# Relay_Sequencer.net
KiCad netlist of a schematic drawn in EAGLE
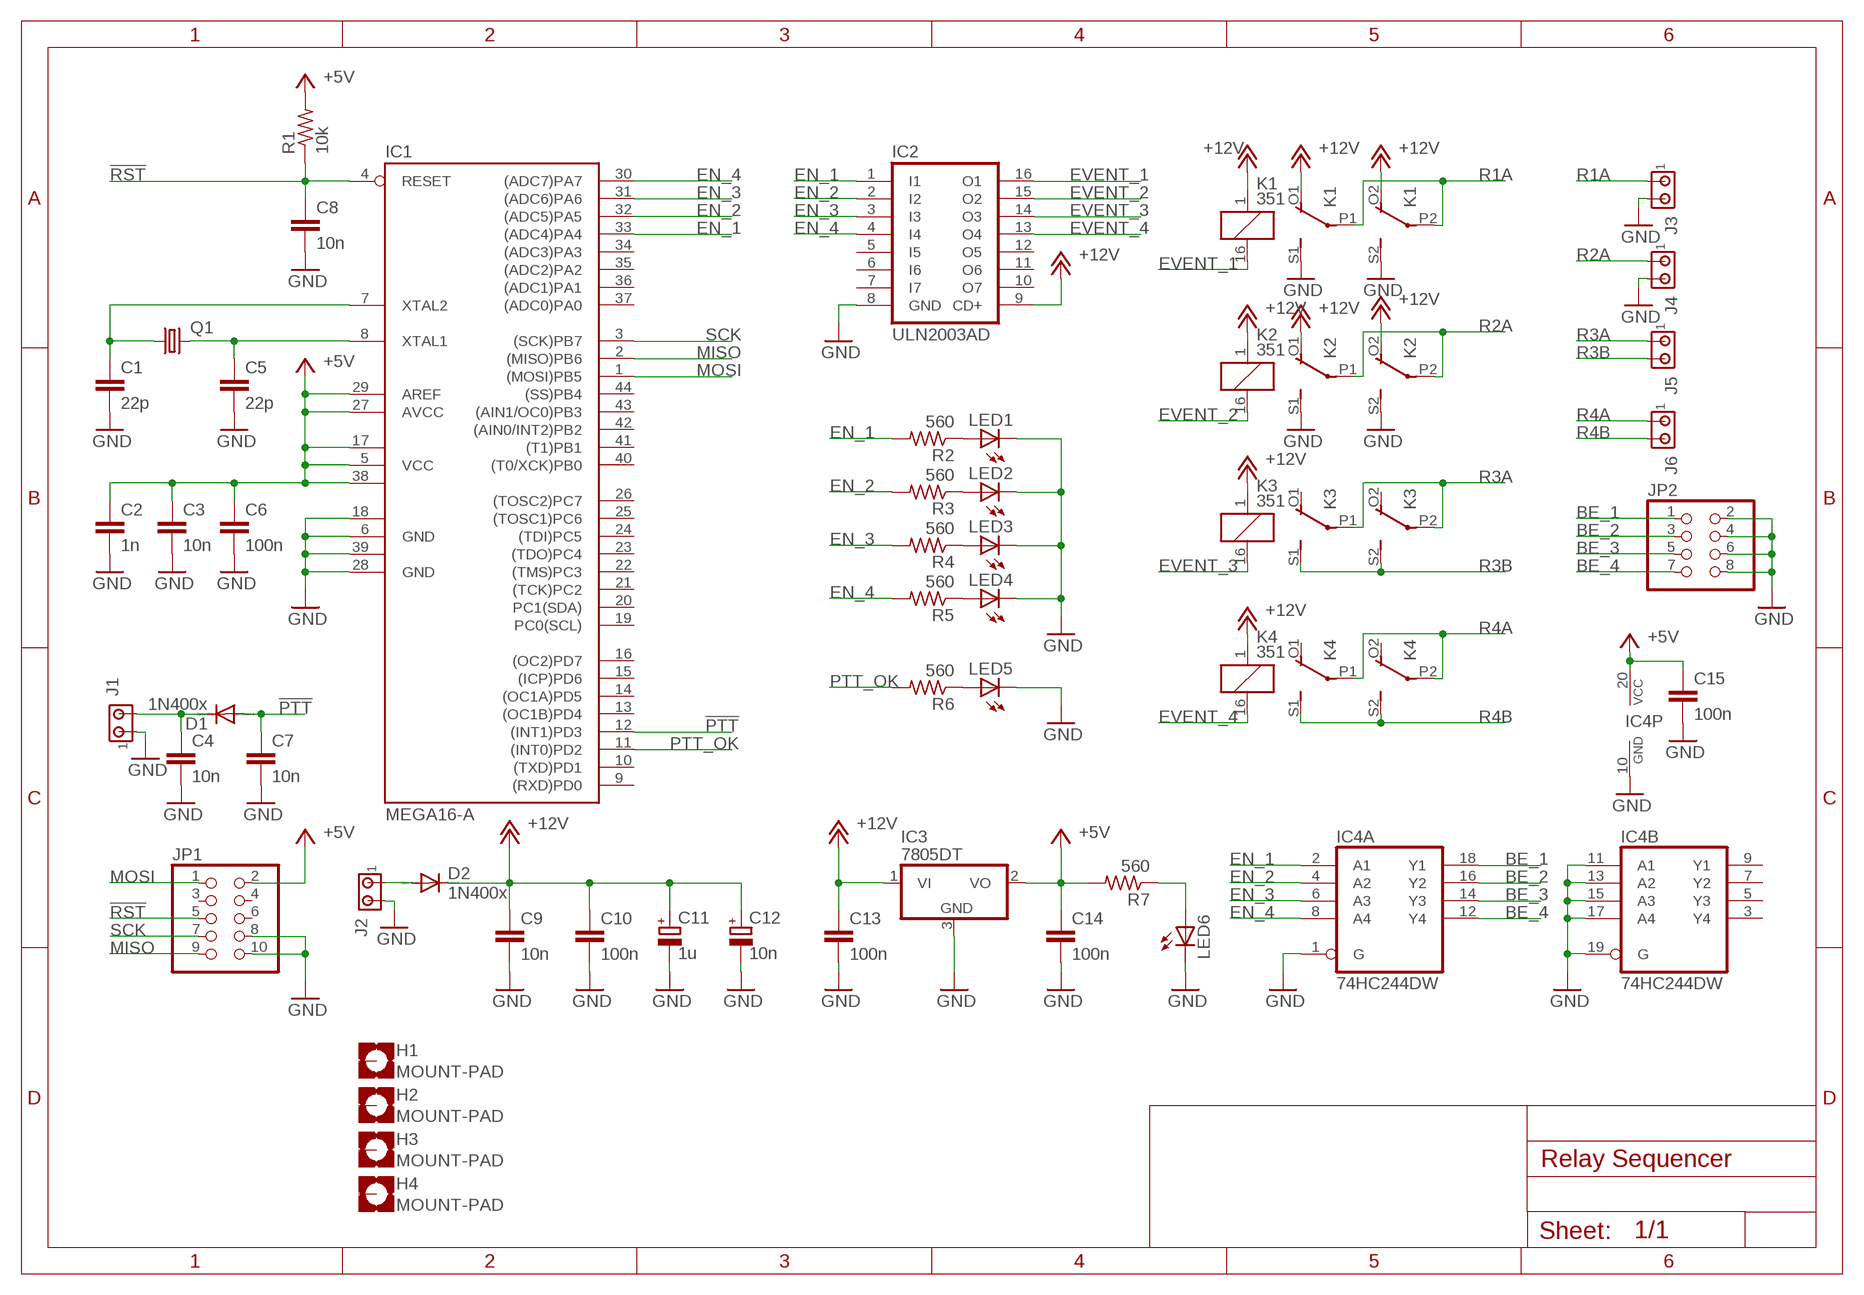
[diagram p0: schematic, sheet 1]

(export (version "E")
  (design (tool "Eeschema 10.0.6"))
  (components
    (comp (ref "C1")
      (value "22p")
      (footprint "eagle-import:C1206")
      (libsource (lib "eagle-import") (part "C-EUC1206"))
    )
    (comp (ref "C2")
      (value "1n")
      (footprint "eagle-import:C1206")
      (libsource (lib "eagle-import") (part "C-EUC1206"))
    )
    (comp (ref "C3")
      (value "10n")
      (footprint "eagle-import:C1206")
      (libsource (lib "eagle-import") (part "C-EUC1206"))
    )
    (comp (ref "C4")
      (value "10n")
      (footprint "eagle-import:C1206")
      (libsource (lib "eagle-import") (part "C-EUC1206"))
    )
    (comp (ref "C5")
      (value "22p")
      (footprint "eagle-import:C1206")
      (libsource (lib "eagle-import") (part "C-EUC1206"))
    )
    (comp (ref "C6")
      (value "100n")
      (footprint "eagle-import:C1206")
      (libsource (lib "eagle-import") (part "C-EUC1206"))
    )
    (comp (ref "C7")
      (value "10n")
      (footprint "eagle-import:C1206")
      (libsource (lib "eagle-import") (part "C-EUC1206"))
    )
    (comp (ref "C8")
      (value "10n")
      (footprint "eagle-import:C1206")
      (libsource (lib "eagle-import") (part "C-EUC1206"))
    )
    (comp (ref "C9")
      (value "10n")
      (footprint "eagle-import:C1206")
      (libsource (lib "eagle-import") (part "C-EUC1206"))
    )
    (comp (ref "C10")
      (value "100n")
      (footprint "eagle-import:C1206")
      (libsource (lib "eagle-import") (part "C-EUC1206"))
    )
    (comp (ref "C11")
      (value "1u")
      (footprint "eagle-import:E5-8,5")
      (libsource (lib "eagle-import") (part "CPOL-EUE5-8.5"))
    )
    (comp (ref "C12")
      (value "10n")
      (footprint "eagle-import:E5-13")
      (libsource (lib "eagle-import") (part "CPOL-EUE5-13"))
    )
    (comp (ref "C13")
      (value "100n")
      (footprint "eagle-import:C1206")
      (libsource (lib "eagle-import") (part "C-EUC1206"))
    )
    (comp (ref "C14")
      (value "100n")
      (footprint "eagle-import:C1206")
      (libsource (lib "eagle-import") (part "C-EUC1206"))
    )
    (comp (ref "C15")
      (value "100n")
      (footprint "eagle-import:C1206")
      (libsource (lib "eagle-import") (part "C-EUC1206"))
    )
    (comp (ref "D1")
      (value "1N400x")
      (footprint "eagle-import:DO35-10")
      (libsource (lib "eagle-import") (part "1N4148DO35-10"))
    )
    (comp (ref "D2")
      (value "1N400x")
      (footprint "eagle-import:DO35-10")
      (libsource (lib "eagle-import") (part "1N4148DO35-10"))
    )
    (comp (ref "H1")
      (value "MOUNT-PAD")
      (footprint "eagle-import:2,8-PAD-SQUARE")
      (libsource (lib "eagle-import") (part "MOUNT-PAD-SQUARE2.8"))
    )
    (comp (ref "H2")
      (value "MOUNT-PAD")
      (footprint "eagle-import:2,8-PAD-SQUARE")
      (libsource (lib "eagle-import") (part "MOUNT-PAD-SQUARE2.8"))
    )
    (comp (ref "H3")
      (value "MOUNT-PAD")
      (footprint "eagle-import:2,8-PAD-SQUARE")
      (libsource (lib "eagle-import") (part "MOUNT-PAD-SQUARE2.8"))
    )
    (comp (ref "H4")
      (value "MOUNT-PAD")
      (footprint "eagle-import:2,8-PAD-SQUARE")
      (libsource (lib "eagle-import") (part "MOUNT-PAD-SQUARE2.8"))
    )
    (comp (ref "IC1")
      (value "MEGA16-A")
      (footprint "eagle-import:TQFP44")
      (fields (field (name "MPN") "ATMEGA16-16AU"))
      (libsource (lib "eagle-import") (part "MEGA16-A"))
    )
    (comp (ref "IC2")
      (value "ULN2003AD")
      (footprint "eagle-import:SO16")
      (libsource (lib "eagle-import") (part "ULN2003AD"))
    )
    (comp (ref "IC3")
      (value "7805DT")
      (footprint "eagle-import:TO252")
      (libsource (lib "eagle-import") (part "78DT05"))
    )
    (comp (ref "IC4")
      (value "74HC244DW")
      (footprint "eagle-import:SO20W")
      (libsource (lib "eagle-import") (part "74244DWHC"))
    )
    (comp (ref "J1")
      (value "MTA02-156")
      (footprint "eagle-import:1X2MTA")
      (libsource (lib "eagle-import") (part "MTA02-156"))
    )
    (comp (ref "J2")
      (value "MTA02-156")
      (footprint "eagle-import:1X2MTA")
      (libsource (lib "eagle-import") (part "MTA02-156"))
    )
    (comp (ref "J3")
      (value "MTA02-156")
      (footprint "eagle-import:1X2MTA")
      (libsource (lib "eagle-import") (part "MTA02-156"))
    )
    (comp (ref "J4")
      (value "MTA02-156")
      (footprint "eagle-import:1X2MTA")
      (libsource (lib "eagle-import") (part "MTA02-156"))
    )
    (comp (ref "J5")
      (value "MTA02-156")
      (footprint "eagle-import:1X2MTA")
      (libsource (lib "eagle-import") (part "MTA02-156"))
    )
    (comp (ref "J6")
      (value "MTA02-156")
      (footprint "eagle-import:1X2MTA")
      (libsource (lib "eagle-import") (part "MTA02-156"))
    )
    (comp (ref "JP1")
      (value "PINHD-2X5")
      (footprint "eagle-import:2X05")
      (libsource (lib "eagle-import") (part "PINHD-2X5"))
    )
    (comp (ref "JP2")
      (value "PINHD-2X4")
      (footprint "eagle-import:2X04")
      (libsource (lib "eagle-import") (part "PINHD-2X4"))
    )
    (comp (ref "K1")
      (value "351")
      (footprint "eagle-import:351")
      (libsource (lib "eagle-import") (part "351"))
    )
    (comp (ref "K2")
      (value "351")
      (footprint "eagle-import:351")
      (libsource (lib "eagle-import") (part "351"))
    )
    (comp (ref "K3")
      (value "351")
      (footprint "eagle-import:351")
      (libsource (lib "eagle-import") (part "351"))
    )
    (comp (ref "K4")
      (value "351")
      (footprint "eagle-import:351")
      (libsource (lib "eagle-import") (part "351"))
    )
    (comp (ref "LED1")
      (value "LED3MM")
      (footprint "eagle-import:LED3MM")
      (libsource (lib "eagle-import") (part "LED3MM"))
    )
    (comp (ref "LED2")
      (value "LED3MM")
      (footprint "eagle-import:LED3MM")
      (libsource (lib "eagle-import") (part "LED3MM"))
    )
    (comp (ref "LED3")
      (value "LED3MM")
      (footprint "eagle-import:LED3MM")
      (libsource (lib "eagle-import") (part "LED3MM"))
    )
    (comp (ref "LED4")
      (value "LED3MM")
      (footprint "eagle-import:LED3MM")
      (libsource (lib "eagle-import") (part "LED3MM"))
    )
    (comp (ref "LED5")
      (value "LED3MM")
      (footprint "eagle-import:LED3MM")
      (libsource (lib "eagle-import") (part "LED3MM"))
    )
    (comp (ref "LED6")
      (value "LED3MM")
      (footprint "eagle-import:LED3MM")
      (libsource (lib "eagle-import") (part "LED3MM"))
    )
    (comp (ref "Q1")
      (value "CRYSTALHC49S")
      (footprint "eagle-import:HC49_S")
      (libsource (lib "eagle-import") (part "CRYSTALHC49S"))
    )
    (comp (ref "R1")
      (value "10k")
      (footprint "eagle-import:M1206")
      (libsource (lib "eagle-import") (part "R-US_M1206"))
    )
    (comp (ref "R2")
      (value "560")
      (footprint "eagle-import:M1206")
      (libsource (lib "eagle-import") (part "R-US_M1206"))
    )
    (comp (ref "R3")
      (value "560")
      (footprint "eagle-import:M1206")
      (libsource (lib "eagle-import") (part "R-US_M1206"))
    )
    (comp (ref "R4")
      (value "560")
      (footprint "eagle-import:M1206")
      (libsource (lib "eagle-import") (part "R-US_M1206"))
    )
    (comp (ref "R5")
      (value "560")
      (footprint "eagle-import:M1206")
      (libsource (lib "eagle-import") (part "R-US_M1206"))
    )
    (comp (ref "R6")
      (value "560")
      (footprint "eagle-import:M1206")
      (libsource (lib "eagle-import") (part "R-US_M1206"))
    )
    (comp (ref "R7")
      (value "560")
      (footprint "eagle-import:M1206")
      (libsource (lib "eagle-import") (part "R-US_M1206"))
    )
  )
  (nets
    (net (code "1") (name "+5V") (class "Default")
      (node (ref "C14") (pin "1") (pinfunction "1_1") (pintype "passive"))
      (node (ref "C15") (pin "1") (pinfunction "1_1") (pintype "passive"))
      (node (ref "C2") (pin "1") (pinfunction "1_1") (pintype "passive"))
      (node (ref "C3") (pin "1") (pinfunction "1_1") (pintype "passive"))
      (node (ref "C6") (pin "1") (pinfunction "1_1") (pintype "passive"))
      (node (ref "IC1") (pin "17") (pinfunction "VCC1_17") (pintype "power_in"))
      (node (ref "IC1") (pin "27") (pinfunction "AVCC_27") (pintype "power_in"))
      (node (ref "IC1") (pin "29") (pinfunction "AREF_29") (pintype "passive"))
      (node (ref "IC1") (pin "38") (pinfunction "VCC2_38") (pintype "power_in"))
      (node (ref "IC1") (pin "5") (pinfunction "VCC_5") (pintype "power_in"))
      (node (ref "IC3") (pin "2") (pinfunction "VO_2") (pintype "passive"))
      (node (ref "IC4") (pin "20") (pinfunction "VCC_20") (pintype "power_in"))
      (node (ref "JP1") (pin "2") (pinfunction "2_2") (pintype "passive"))
      (node (ref "R1") (pin "2") (pinfunction "2_2") (pintype "passive"))
      (node (ref "R7") (pin "2") (pinfunction "2_2") (pintype "passive"))
    )
    (net (code "2") (name "+12V") (class "Default")
      (node (ref "C10") (pin "1") (pinfunction "1_1") (pintype "passive"))
      (node (ref "C11") (pin "+") (pinfunction "+_+") (pintype "passive"))
      (node (ref "C12") (pin "+") (pinfunction "+_+") (pintype "passive"))
      (node (ref "C13") (pin "1") (pinfunction "1_1") (pintype "passive"))
      (node (ref "C9") (pin "1") (pinfunction "1_1") (pintype "passive"))
      (node (ref "D2") (pin "C") (pinfunction "C_C") (pintype "passive"))
      (node (ref "IC2") (pin "9") (pinfunction "CD+_9") (pintype "passive"))
      (node (ref "IC3") (pin "1") (pinfunction "VI_1") (pintype "input"))
      (node (ref "K1") (pin "1") (pinfunction "1_1") (pintype "passive"))
      (node (ref "K1") (pin "O1") (pinfunction "O_O1") (pintype "passive"))
      (node (ref "K1") (pin "O2") (pinfunction "O_O2") (pintype "passive"))
      (node (ref "K2") (pin "1") (pinfunction "1_1") (pintype "passive"))
      (node (ref "K2") (pin "O1") (pinfunction "O_O1") (pintype "passive"))
      (node (ref "K2") (pin "O2") (pinfunction "O_O2") (pintype "passive"))
      (node (ref "K3") (pin "1") (pinfunction "1_1") (pintype "passive"))
      (node (ref "K4") (pin "1") (pinfunction "1_1") (pintype "passive"))
    )
    (net (code "3") (name "/BE_1") (class "Default")
      (node (ref "IC4") (pin "18") (pinfunction "Y1_18") (pintype "tri_state"))
      (node (ref "JP2") (pin "1") (pinfunction "1_1") (pintype "passive"))
    )
    (net (code "4") (name "/BE_2") (class "Default")
      (node (ref "IC4") (pin "16") (pinfunction "Y2_16") (pintype "tri_state"))
      (node (ref "JP2") (pin "3") (pinfunction "3_3") (pintype "passive"))
    )
    (net (code "5") (name "/BE_3") (class "Default")
      (node (ref "IC4") (pin "14") (pinfunction "Y3_14") (pintype "tri_state"))
      (node (ref "JP2") (pin "5") (pinfunction "5_5") (pintype "passive"))
    )
    (net (code "6") (name "/BE_4") (class "Default")
      (node (ref "IC4") (pin "12") (pinfunction "Y4_12") (pintype "tri_state"))
      (node (ref "JP2") (pin "7") (pinfunction "7_7") (pintype "passive"))
    )
    (net (code "7") (name "/EN_1") (class "Default")
      (node (ref "IC1") (pin "33") (pinfunction "(ADC4)PA4_33") (pintype "bidirectional"))
      (node (ref "IC2") (pin "1") (pinfunction "I1_1") (pintype "input"))
      (node (ref "IC4") (pin "2") (pinfunction "A1_2") (pintype "input"))
      (node (ref "R2") (pin "2") (pinfunction "2_2") (pintype "passive"))
    )
    (net (code "8") (name "/EN_2") (class "Default")
      (node (ref "IC1") (pin "32") (pinfunction "(ADC5)PA5_32") (pintype "bidirectional"))
      (node (ref "IC2") (pin "2") (pinfunction "I2_2") (pintype "input"))
      (node (ref "IC4") (pin "4") (pinfunction "A2_4") (pintype "input"))
      (node (ref "R3") (pin "2") (pinfunction "2_2") (pintype "passive"))
    )
    (net (code "9") (name "/EN_3") (class "Default")
      (node (ref "IC1") (pin "31") (pinfunction "(ADC6)PA6_31") (pintype "bidirectional"))
      (node (ref "IC2") (pin "3") (pinfunction "I3_3") (pintype "input"))
      (node (ref "IC4") (pin "6") (pinfunction "A3_6") (pintype "input"))
      (node (ref "R4") (pin "2") (pinfunction "2_2") (pintype "passive"))
    )
    (net (code "10") (name "/EN_4") (class "Default")
      (node (ref "IC1") (pin "30") (pinfunction "(ADC7)PA7_30") (pintype "bidirectional"))
      (node (ref "IC2") (pin "4") (pinfunction "I4_4") (pintype "input"))
      (node (ref "IC4") (pin "8") (pinfunction "A4_8") (pintype "input"))
      (node (ref "R5") (pin "2") (pinfunction "2_2") (pintype "passive"))
    )
    (net (code "11") (name "/EVENT_1") (class "Default")
      (node (ref "IC2") (pin "16") (pinfunction "O1_16") (pintype "open_collector"))
      (node (ref "K1") (pin "16") (pinfunction "2_16") (pintype "passive"))
    )
    (net (code "12") (name "/EVENT_2") (class "Default")
      (node (ref "IC2") (pin "15") (pinfunction "O2_15") (pintype "open_collector"))
      (node (ref "K2") (pin "16") (pinfunction "2_16") (pintype "passive"))
    )
    (net (code "13") (name "/EVENT_3") (class "Default")
      (node (ref "IC2") (pin "14") (pinfunction "O3_14") (pintype "open_collector"))
      (node (ref "K3") (pin "16") (pinfunction "2_16") (pintype "passive"))
    )
    (net (code "14") (name "/EVENT_4") (class "Default")
      (node (ref "IC2") (pin "13") (pinfunction "O4_13") (pintype "open_collector"))
      (node (ref "K4") (pin "16") (pinfunction "2_16") (pintype "passive"))
    )
    (net (code "15") (name "/MISO") (class "Default")
      (node (ref "IC1") (pin "2") (pinfunction "(MISO)PB6_2") (pintype "bidirectional"))
      (node (ref "JP1") (pin "9") (pinfunction "9_9") (pintype "passive"))
    )
    (net (code "16") (name "/MOSI") (class "Default")
      (node (ref "IC1") (pin "1") (pinfunction "(MOSI)PB5_1") (pintype "bidirectional"))
      (node (ref "JP1") (pin "1") (pinfunction "1_1") (pintype "passive"))
    )
    (net (code "17") (name "/PTT_OK") (class "Default")
      (node (ref "IC1") (pin "11") (pinfunction "(INT0)PD2_11") (pintype "bidirectional"))
      (node (ref "R6") (pin "2") (pinfunction "2_2") (pintype "passive"))
    )
    (net (code "18") (name "/R1A") (class "Default")
      (node (ref "J3") (pin "1") (pinfunction "1_1") (pintype "passive"))
      (node (ref "K1") (pin "P1") (pinfunction "P_P1") (pintype "passive"))
      (node (ref "K1") (pin "P2") (pinfunction "P_P2") (pintype "passive"))
    )
    (net (code "19") (name "/R2A") (class "Default")
      (node (ref "J4") (pin "1") (pinfunction "1_1") (pintype "passive"))
      (node (ref "K2") (pin "P1") (pinfunction "P_P1") (pintype "passive"))
      (node (ref "K2") (pin "P2") (pinfunction "P_P2") (pintype "passive"))
    )
    (net (code "20") (name "/R3A") (class "Default")
      (node (ref "J5") (pin "1") (pinfunction "1_1") (pintype "passive"))
      (node (ref "K3") (pin "P1") (pinfunction "P_P1") (pintype "passive"))
      (node (ref "K3") (pin "P2") (pinfunction "P_P2") (pintype "passive"))
    )
    (net (code "21") (name "/R3B") (class "Default")
      (node (ref "J5") (pin "2") (pinfunction "2_2") (pintype "passive"))
      (node (ref "K3") (pin "S1") (pinfunction "S_S1") (pintype "passive"))
      (node (ref "K3") (pin "S2") (pinfunction "S_S2") (pintype "passive"))
    )
    (net (code "22") (name "/R4A") (class "Default")
      (node (ref "J6") (pin "1") (pinfunction "1_1") (pintype "passive"))
      (node (ref "K4") (pin "P1") (pinfunction "P_P1") (pintype "passive"))
      (node (ref "K4") (pin "P2") (pinfunction "P_P2") (pintype "passive"))
    )
    (net (code "23") (name "/R4B") (class "Default")
      (node (ref "J6") (pin "2") (pinfunction "2_2") (pintype "passive"))
      (node (ref "K4") (pin "S1") (pinfunction "S_S1") (pintype "passive"))
      (node (ref "K4") (pin "S2") (pinfunction "S_S2") (pintype "passive"))
    )
    (net (code "24") (name "/SCK") (class "Default")
      (node (ref "IC1") (pin "3") (pinfunction "(SCK)PB7_3") (pintype "bidirectional"))
      (node (ref "JP1") (pin "7") (pinfunction "7_7") (pintype "passive"))
    )
    (net (code "25") (name "/~{PTT}") (class "Default")
      (node (ref "C7") (pin "1") (pinfunction "1_1") (pintype "passive"))
      (node (ref "D1") (pin "A") (pinfunction "A_A") (pintype "passive"))
      (node (ref "IC1") (pin "12") (pinfunction "(INT1)PD3_12") (pintype "bidirectional"))
    )
    (net (code "26") (name "/~{RST}") (class "Default")
      (node (ref "C8") (pin "1") (pinfunction "1_1") (pintype "passive"))
      (node (ref "IC1") (pin "4") (pinfunction "RESET_4") (pintype "input"))
      (node (ref "JP1") (pin "5") (pinfunction "5_5") (pintype "passive"))
      (node (ref "R1") (pin "1") (pinfunction "1_1") (pintype "passive"))
    )
    (net (code "27") (name "GND") (class "Default")
      (node (ref "C1") (pin "2") (pinfunction "2_2") (pintype "passive"))
      (node (ref "C10") (pin "2") (pinfunction "2_2") (pintype "passive"))
      (node (ref "C11") (pin "-") (pinfunction "-_-") (pintype "passive"))
      (node (ref "C12") (pin "-") (pinfunction "-_-") (pintype "passive"))
      (node (ref "C13") (pin "2") (pinfunction "2_2") (pintype "passive"))
      (node (ref "C14") (pin "2") (pinfunction "2_2") (pintype "passive"))
      (node (ref "C15") (pin "2") (pinfunction "2_2") (pintype "passive"))
      (node (ref "C2") (pin "2") (pinfunction "2_2") (pintype "passive"))
      (node (ref "C3") (pin "2") (pinfunction "2_2") (pintype "passive"))
      (node (ref "C4") (pin "2") (pinfunction "2_2") (pintype "passive"))
      (node (ref "C5") (pin "2") (pinfunction "2_2") (pintype "passive"))
      (node (ref "C6") (pin "2") (pinfunction "2_2") (pintype "passive"))
      (node (ref "C7") (pin "2") (pinfunction "2_2") (pintype "passive"))
      (node (ref "C8") (pin "2") (pinfunction "2_2") (pintype "passive"))
      (node (ref "C9") (pin "2") (pinfunction "2_2") (pintype "passive"))
      (node (ref "IC1") (pin "18") (pinfunction "GND1_18") (pintype "power_in"))
      (node (ref "IC1") (pin "28") (pinfunction "GND_28") (pintype "power_in"))
      (node (ref "IC1") (pin "39") (pinfunction "GND2_39") (pintype "power_in"))
      (node (ref "IC1") (pin "6") (pinfunction "GND_6") (pintype "power_in"))
      (node (ref "IC2") (pin "8") (pinfunction "GND_8") (pintype "power_in"))
      (node (ref "IC3") (pin "3") (pinfunction "GND_3") (pintype "passive"))
      (node (ref "IC4") (pin "1") (pinfunction "G_1") (pintype "input"))
      (node (ref "IC4") (pin "10") (pinfunction "GND_10") (pintype "power_in"))
      (node (ref "IC4") (pin "11") (pinfunction "A1_11") (pintype "input"))
      (node (ref "IC4") (pin "13") (pinfunction "A2_13") (pintype "input"))
      (node (ref "IC4") (pin "15") (pinfunction "A3_15") (pintype "input"))
      (node (ref "IC4") (pin "17") (pinfunction "A4_17") (pintype "input"))
      (node (ref "IC4") (pin "19") (pinfunction "G_19") (pintype "input"))
      (node (ref "J1") (pin "1") (pinfunction "1_1") (pintype "passive"))
      (node (ref "J2") (pin "2") (pinfunction "2_2") (pintype "passive"))
      (node (ref "J3") (pin "2") (pinfunction "2_2") (pintype "passive"))
      (node (ref "J4") (pin "2") (pinfunction "2_2") (pintype "passive"))
      (node (ref "JP1") (pin "10") (pinfunction "10_10") (pintype "passive"))
      (node (ref "JP1") (pin "8") (pinfunction "8_8") (pintype "passive"))
      (node (ref "JP2") (pin "2") (pinfunction "2_2") (pintype "passive"))
      (node (ref "JP2") (pin "4") (pinfunction "4_4") (pintype "passive"))
      (node (ref "JP2") (pin "6") (pinfunction "6_6") (pintype "passive"))
      (node (ref "JP2") (pin "8") (pinfunction "8_8") (pintype "passive"))
      (node (ref "K1") (pin "S1") (pinfunction "S_S1") (pintype "passive"))
      (node (ref "K1") (pin "S2") (pinfunction "S_S2") (pintype "passive"))
      (node (ref "K2") (pin "S1") (pinfunction "S_S1") (pintype "passive"))
      (node (ref "K2") (pin "S2") (pinfunction "S_S2") (pintype "passive"))
      (node (ref "LED1") (pin "K") (pinfunction "C_K") (pintype "passive"))
      (node (ref "LED2") (pin "K") (pinfunction "C_K") (pintype "passive"))
      (node (ref "LED3") (pin "K") (pinfunction "C_K") (pintype "passive"))
      (node (ref "LED4") (pin "K") (pinfunction "C_K") (pintype "passive"))
      (node (ref "LED5") (pin "K") (pinfunction "C_K") (pintype "passive"))
      (node (ref "LED6") (pin "K") (pinfunction "C_K") (pintype "passive"))
    )
    (net (code "28") (name "Net-(C4-Pad1)") (class "Default")
      (node (ref "C4") (pin "1") (pinfunction "1_1") (pintype "passive"))
      (node (ref "D1") (pin "C") (pinfunction "C_C") (pintype "passive"))
      (node (ref "J1") (pin "2") (pinfunction "2_2") (pintype "passive"))
    )
    (net (code "29") (name "Net-(D2-PadA)") (class "Default")
      (node (ref "D2") (pin "A") (pinfunction "A_A") (pintype "passive"))
      (node (ref "J2") (pin "1") (pinfunction "1_1") (pintype "passive"))
    )
    (net (code "30") (name "Net-(IC1-XTAL1)") (class "Default")
      (node (ref "C5") (pin "1") (pinfunction "1_1") (pintype "passive"))
      (node (ref "IC1") (pin "8") (pinfunction "XTAL1_8") (pintype "bidirectional"))
      (node (ref "Q1") (pin "2") (pinfunction "2_2") (pintype "passive"))
    )
    (net (code "31") (name "Net-(IC1-XTAL2)") (class "Default")
      (node (ref "C1") (pin "1") (pinfunction "1_1") (pintype "passive"))
      (node (ref "IC1") (pin "7") (pinfunction "XTAL2_7") (pintype "bidirectional"))
      (node (ref "Q1") (pin "1") (pinfunction "1_1") (pintype "passive"))
    )
    (net (code "32") (name "Net-(LED1-PadA)") (class "Default")
      (node (ref "LED1") (pin "A") (pinfunction "A_A") (pintype "passive"))
      (node (ref "R2") (pin "1") (pinfunction "1_1") (pintype "passive"))
    )
    (net (code "33") (name "Net-(LED2-PadA)") (class "Default")
      (node (ref "LED2") (pin "A") (pinfunction "A_A") (pintype "passive"))
      (node (ref "R3") (pin "1") (pinfunction "1_1") (pintype "passive"))
    )
    (net (code "34") (name "Net-(LED3-PadA)") (class "Default")
      (node (ref "LED3") (pin "A") (pinfunction "A_A") (pintype "passive"))
      (node (ref "R4") (pin "1") (pinfunction "1_1") (pintype "passive"))
    )
    (net (code "35") (name "Net-(LED4-PadA)") (class "Default")
      (node (ref "LED4") (pin "A") (pinfunction "A_A") (pintype "passive"))
      (node (ref "R5") (pin "1") (pinfunction "1_1") (pintype "passive"))
    )
    (net (code "36") (name "Net-(LED5-PadA)") (class "Default")
      (node (ref "LED5") (pin "A") (pinfunction "A_A") (pintype "passive"))
      (node (ref "R6") (pin "1") (pinfunction "1_1") (pintype "passive"))
    )
    (net (code "37") (name "Net-(LED6-PadA)") (class "Default")
      (node (ref "LED6") (pin "A") (pinfunction "A_A") (pintype "passive"))
      (node (ref "R7") (pin "1") (pinfunction "1_1") (pintype "passive"))
    )
    (net (code "38") (name "unconnected-(H1-MOUNT-PadB2,8)") (class "Default")
      (node (ref "H1") (pin "B2,8") (pinfunction "MOUNT_B2,8") (pintype "passive"))
    )
    (net (code "39") (name "unconnected-(H2-MOUNT-PadB2,8)") (class "Default")
      (node (ref "H2") (pin "B2,8") (pinfunction "MOUNT_B2,8") (pintype "passive"))
    )
    (net (code "40") (name "unconnected-(H3-MOUNT-PadB2,8)") (class "Default")
      (node (ref "H3") (pin "B2,8") (pinfunction "MOUNT_B2,8") (pintype "passive"))
    )
    (net (code "41") (name "unconnected-(H4-MOUNT-PadB2,8)") (class "Default")
      (node (ref "H4") (pin "B2,8") (pinfunction "MOUNT_B2,8") (pintype "passive"))
    )
    (net (code "42") (name "unconnected-(IC1-(ADC0)PA0-Pad37)") (class "Default")
      (node (ref "IC1") (pin "37") (pinfunction "(ADC0)PA0_37") (pintype "bidirectional"))
    )
    (net (code "43") (name "unconnected-(IC1-(ADC1)PA1-Pad36)") (class "Default")
      (node (ref "IC1") (pin "36") (pinfunction "(ADC1)PA1_36") (pintype "bidirectional"))
    )
    (net (code "44") (name "unconnected-(IC1-(ADC2)PA2-Pad35)") (class "Default")
      (node (ref "IC1") (pin "35") (pinfunction "(ADC2)PA2_35") (pintype "bidirectional"))
    )
    (net (code "45") (name "unconnected-(IC1-(ADC3)PA3-Pad34)") (class "Default")
      (node (ref "IC1") (pin "34") (pinfunction "(ADC3)PA3_34") (pintype "bidirectional"))
    )
    (net (code "46") (name "unconnected-(IC1-(AIN0{slash}INT2)PB2-Pad42)") (class "Default")
      (node (ref "IC1") (pin "42") (pinfunction "(AIN0/INT2)PB2_42") (pintype "bidirectional"))
    )
    (net (code "47") (name "unconnected-(IC1-(AIN1{slash}OC0)PB3-Pad43)") (class "Default")
      (node (ref "IC1") (pin "43") (pinfunction "(AIN1/OC0)PB3_43") (pintype "bidirectional"))
    )
    (net (code "48") (name "unconnected-(IC1-(ICP)PD6-Pad15)") (class "Default")
      (node (ref "IC1") (pin "15") (pinfunction "(ICP)PD6_15") (pintype "bidirectional"))
    )
    (net (code "49") (name "unconnected-(IC1-(OC1A)PD5-Pad14)") (class "Default")
      (node (ref "IC1") (pin "14") (pinfunction "(OC1A)PD5_14") (pintype "bidirectional"))
    )
    (net (code "50") (name "unconnected-(IC1-(OC1B)PD4-Pad13)") (class "Default")
      (node (ref "IC1") (pin "13") (pinfunction "(OC1B)PD4_13") (pintype "bidirectional"))
    )
    (net (code "51") (name "unconnected-(IC1-(OC2)PD7-Pad16)") (class "Default")
      (node (ref "IC1") (pin "16") (pinfunction "(OC2)PD7_16") (pintype "bidirectional"))
    )
    (net (code "52") (name "unconnected-(IC1-(RXD)PD0-Pad9)") (class "Default")
      (node (ref "IC1") (pin "9") (pinfunction "(RXD)PD0_9") (pintype "bidirectional"))
    )
    (net (code "53") (name "unconnected-(IC1-(SS)PB4-Pad44)") (class "Default")
      (node (ref "IC1") (pin "44") (pinfunction "(SS)PB4_44") (pintype "bidirectional"))
    )
    (net (code "54") (name "unconnected-(IC1-(T0{slash}XCK)PB0-Pad40)") (class "Default")
      (node (ref "IC1") (pin "40") (pinfunction "(T0/XCK)PB0_40") (pintype "bidirectional"))
    )
    (net (code "55") (name "unconnected-(IC1-(T1)PB1-Pad41)") (class "Default")
      (node (ref "IC1") (pin "41") (pinfunction "(T1)PB1_41") (pintype "bidirectional"))
    )
    (net (code "56") (name "unconnected-(IC1-(TCK)PC2-Pad21)") (class "Default")
      (node (ref "IC1") (pin "21") (pinfunction "(TCK)PC2_21") (pintype "bidirectional"))
    )
    (net (code "57") (name "unconnected-(IC1-(TDI)PC5-Pad24)") (class "Default")
      (node (ref "IC1") (pin "24") (pinfunction "(TDI)PC5_24") (pintype "bidirectional"))
    )
    (net (code "58") (name "unconnected-(IC1-(TDO)PC4-Pad23)") (class "Default")
      (node (ref "IC1") (pin "23") (pinfunction "(TDO)PC4_23") (pintype "bidirectional"))
    )
    (net (code "59") (name "unconnected-(IC1-(TMS)PC3-Pad22)") (class "Default")
      (node (ref "IC1") (pin "22") (pinfunction "(TMS)PC3_22") (pintype "bidirectional"))
    )
    (net (code "60") (name "unconnected-(IC1-(TOSC1)PC6-Pad25)") (class "Default")
      (node (ref "IC1") (pin "25") (pinfunction "(TOSC1)PC6_25") (pintype "bidirectional"))
    )
    (net (code "61") (name "unconnected-(IC1-(TOSC2)PC7-Pad26)") (class "Default")
      (node (ref "IC1") (pin "26") (pinfunction "(TOSC2)PC7_26") (pintype "bidirectional"))
    )
    (net (code "62") (name "unconnected-(IC1-(TXD)PD1-Pad10)") (class "Default")
      (node (ref "IC1") (pin "10") (pinfunction "(TXD)PD1_10") (pintype "bidirectional"))
    )
    (net (code "63") (name "unconnected-(IC1-PC0(SCL)-Pad19)") (class "Default")
      (node (ref "IC1") (pin "19") (pinfunction "PC0(SCL)_19") (pintype "bidirectional"))
    )
    (net (code "64") (name "unconnected-(IC1-PC1(SDA)-Pad20)") (class "Default")
      (node (ref "IC1") (pin "20") (pinfunction "PC1(SDA)_20") (pintype "bidirectional"))
    )
    (net (code "65") (name "unconnected-(IC2-I5-Pad5)") (class "Default")
      (node (ref "IC2") (pin "5") (pinfunction "I5_5") (pintype "input"))
    )
    (net (code "66") (name "unconnected-(IC2-I6-Pad6)") (class "Default")
      (node (ref "IC2") (pin "6") (pinfunction "I6_6") (pintype "input"))
    )
    (net (code "67") (name "unconnected-(IC2-I7-Pad7)") (class "Default")
      (node (ref "IC2") (pin "7") (pinfunction "I7_7") (pintype "input"))
    )
    (net (code "68") (name "unconnected-(IC2-O5-Pad12)") (class "Default")
      (node (ref "IC2") (pin "12") (pinfunction "O5_12") (pintype "open_collector"))
    )
    (net (code "69") (name "unconnected-(IC2-O6-Pad11)") (class "Default")
      (node (ref "IC2") (pin "11") (pinfunction "O6_11") (pintype "open_collector"))
    )
    (net (code "70") (name "unconnected-(IC2-O7-Pad10)") (class "Default")
      (node (ref "IC2") (pin "10") (pinfunction "O7_10") (pintype "open_collector"))
    )
    (net (code "71") (name "unconnected-(IC4B-Y1-Pad9)") (class "Default")
      (node (ref "IC4") (pin "9") (pinfunction "Y1_9") (pintype "tri_state"))
    )
    (net (code "72") (name "unconnected-(IC4B-Y2-Pad7)") (class "Default")
      (node (ref "IC4") (pin "7") (pinfunction "Y2_7") (pintype "tri_state"))
    )
    (net (code "73") (name "unconnected-(IC4B-Y3-Pad5)") (class "Default")
      (node (ref "IC4") (pin "5") (pinfunction "Y3_5") (pintype "tri_state"))
    )
    (net (code "74") (name "unconnected-(IC4B-Y4-Pad3)") (class "Default")
      (node (ref "IC4") (pin "3") (pinfunction "Y4_3") (pintype "tri_state"))
    )
    (net (code "75") (name "unconnected-(JP1-Pad3)") (class "Default")
      (node (ref "JP1") (pin "3") (pinfunction "3_3") (pintype "passive"))
    )
    (net (code "76") (name "unconnected-(JP1-Pad4)") (class "Default")
      (node (ref "JP1") (pin "4") (pinfunction "4_4") (pintype "passive"))
    )
    (net (code "77") (name "unconnected-(JP1-Pad6)") (class "Default")
      (node (ref "JP1") (pin "6") (pinfunction "6_6") (pintype "passive"))
    )
    (net (code "78") (name "unconnected-(K3B-O-PadO1)") (class "Default")
      (node (ref "K3") (pin "O1") (pinfunction "O_O1") (pintype "passive"))
    )
    (net (code "79") (name "unconnected-(K3C-O-PadO2)") (class "Default")
      (node (ref "K3") (pin "O2") (pinfunction "O_O2") (pintype "passive"))
    )
    (net (code "80") (name "unconnected-(K4B-O-PadO1)") (class "Default")
      (node (ref "K4") (pin "O1") (pinfunction "O_O1") (pintype "passive"))
    )
    (net (code "81") (name "unconnected-(K4C-O-PadO2)") (class "Default")
      (node (ref "K4") (pin "O2") (pinfunction "O_O2") (pintype "passive"))
    )
  )
)
